# Chessbot_v8.net
KiCad netlist of a schematic drawn in EAGLE
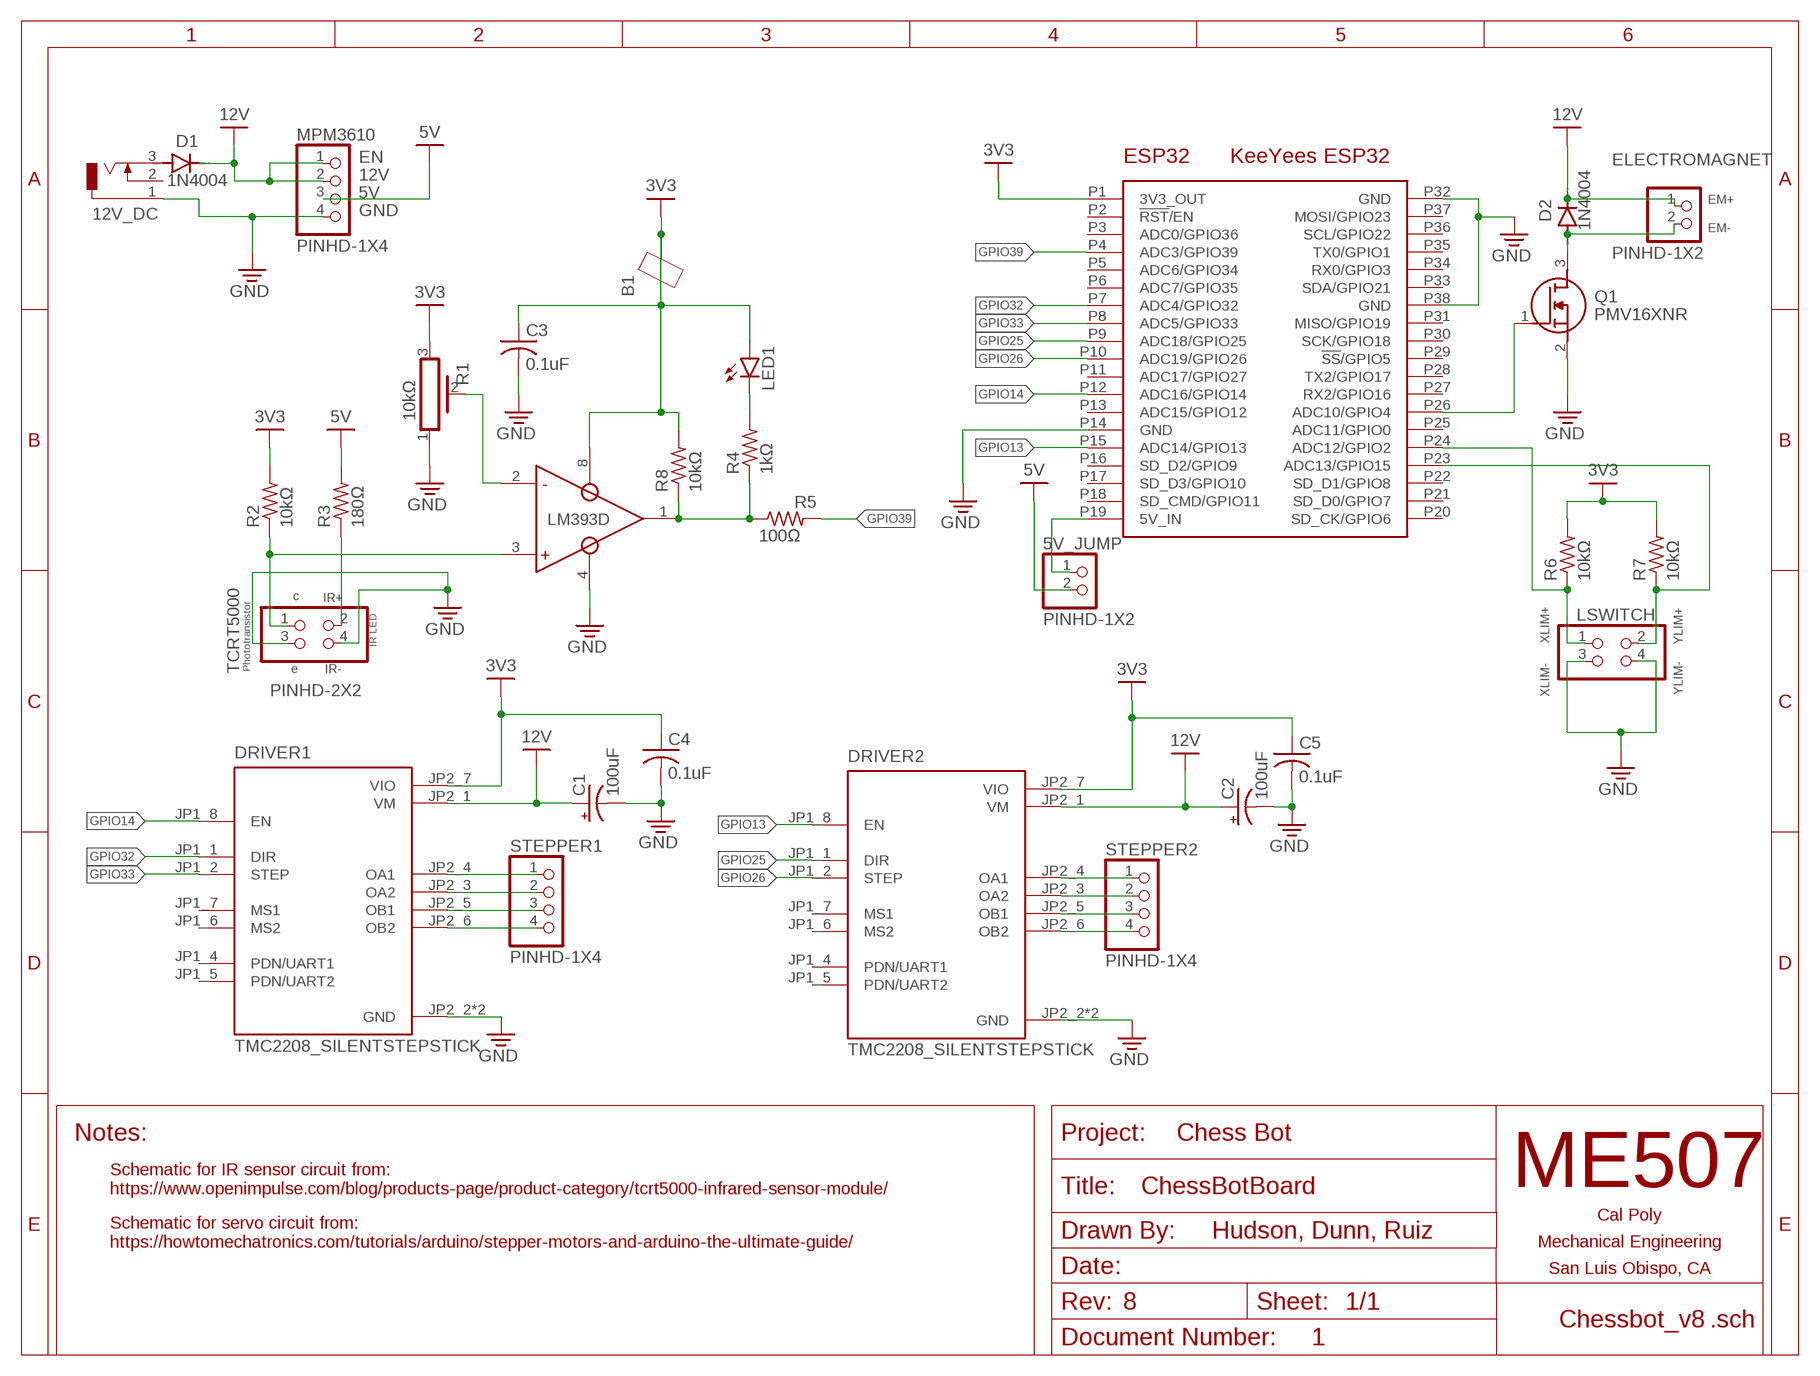
[diagram p0: schematic, sheet 1]

(export (version "E")
  (design (tool "Eeschema 10.0.6"))
  (components
    (comp (ref "5V_JUMP")
      (value "PINHD-1X2")
      (footprint "eagle-import:1X02")
      (libsource (lib "eagle-import") (part "PINHD-1X2"))
    )
    (comp (ref "12V_DC")
      (value "DCJ0303")
      (footprint "eagle-import:DCJ0303")
      (libsource (lib "eagle-import") (part "DCJ0303"))
    )
    (comp (ref "B1")
      (value "BEAD0805")
      (footprint "eagle-import:0805")
      (libsource (lib "eagle-import") (part "BEAD0805"))
    )
    (comp (ref "C1")
      (value "100uF")
      (footprint "eagle-import:E2,5-6")
      (libsource (lib "eagle-import") (part "CPOL-USE2.5-6"))
    )
    (comp (ref "C2")
      (value "100uF")
      (footprint "eagle-import:E2,5-6")
      (libsource (lib "eagle-import") (part "CPOL-USE2.5-6"))
    )
    (comp (ref "C3")
      (value "0.1uF")
      (footprint "eagle-import:C0805")
      (libsource (lib "eagle-import") (part "C-USC0805"))
    )
    (comp (ref "C4")
      (value "0.1uF")
      (footprint "eagle-import:C0805")
      (libsource (lib "eagle-import") (part "C-USC0805"))
    )
    (comp (ref "C5")
      (value "0.1uF")
      (footprint "eagle-import:C0805")
      (libsource (lib "eagle-import") (part "C-USC0805"))
    )
    (comp (ref "D1")
      (value "1N4004")
      (footprint "eagle-import:DO41-10")
      (libsource (lib "eagle-import") (part "1N4004"))
    )
    (comp (ref "D2")
      (value "1N4004")
      (footprint "eagle-import:DO41-10")
      (libsource (lib "eagle-import") (part "1N4004"))
    )
    (comp (ref "DRIVER1")
      (value "TMC2208_SILENTSTEPSTICK")
      (footprint "eagle-import:MODULE_TMC2208_SILENTSTEPSTICK")
      (fields (field (name "MF") "Trinamic Motion") (field (name "MP") "TMC2208 SILENTSTEPSTICK"))
      (libsource (lib "eagle-import") (part "TMC2208_SILENTSTEPSTICK"))
    )
    (comp (ref "DRIVER2")
      (value "TMC2208_SILENTSTEPSTICK")
      (footprint "eagle-import:MODULE_TMC2208_SILENTSTEPSTICK")
      (fields (field (name "MF") "Trinamic Motion") (field (name "MP") "TMC2208 SILENTSTEPSTICK"))
      (libsource (lib "eagle-import") (part "TMC2208_SILENTSTEPSTICK"))
    )
    (comp (ref "ELECTROMAGNET")
      (value "PINHD-1X2")
      (footprint "eagle-import:1X02")
      (libsource (lib "eagle-import") (part "PINHD-1X2"))
    )
    (comp (ref "ESP32")
      (value "KEEYEES_ESP32")
      (footprint "eagle-import:KEEYEES_ESP32")
      (libsource (lib "eagle-import") (part "KEEYEES_ESP32"))
    )
    (comp (ref "LED1")
      (value "LEDSMT1206")
      (footprint "eagle-import:1206")
      (libsource (lib "eagle-import") (part "LEDSMT1206"))
    )
    (comp (ref "LSWITCH")
      (value "PINHD-2X2")
      (footprint "eagle-import:2X02")
      (libsource (lib "eagle-import") (part "pinhead_325_PINHD-2X2"))
    )
    (comp (ref "MPM3610")
      (value "PINHD-1X4")
      (footprint "eagle-import:1X04")
      (libsource (lib "eagle-import") (part "PINHD-1X4"))
    )
    (comp (ref "Q1")
      (value "PMV16XNR")
      (footprint "eagle-import:SOT95P230X110-3N")
      (fields (field (name "MOUSER_PART_NUMBER") "771-PMV16XNR"))
      (libsource (lib "eagle-import") (part "PMV16XNR"))
    )
    (comp (ref "R1")
      (value "10kΩ")
      (footprint "eagle-import:PV36Z")
      (fields (field (name "MANUFACTURER") "BOURNS") (field (name "MPN") "PV36Z"))
      (libsource (lib "eagle-import") (part "PV36Z"))
    )
    (comp (ref "R2")
      (value "10kΩ")
      (footprint "eagle-import:R0805")
      (libsource (lib "eagle-import") (part "R-US_R0805"))
    )
    (comp (ref "R3")
      (value "180Ω")
      (footprint "eagle-import:R0805")
      (libsource (lib "eagle-import") (part "R-US_R0805"))
    )
    (comp (ref "R4")
      (value "1kΩ")
      (footprint "eagle-import:R0805")
      (libsource (lib "eagle-import") (part "R-US_R0805"))
    )
    (comp (ref "R5")
      (value "100Ω")
      (footprint "eagle-import:R0805")
      (libsource (lib "eagle-import") (part "R-US_R0805"))
    )
    (comp (ref "R6")
      (value "10kΩ")
      (footprint "eagle-import:R0805")
      (libsource (lib "eagle-import") (part "R-US_R0805"))
    )
    (comp (ref "R7")
      (value "10kΩ")
      (footprint "eagle-import:R0805")
      (libsource (lib "eagle-import") (part "R-US_R0805"))
    )
    (comp (ref "R8")
      (value "10kΩ")
      (footprint "eagle-import:R0805")
      (libsource (lib "eagle-import") (part "R-US_R0805"))
    )
    (comp (ref "STEPPER1")
      (value "PINHD-1X4")
      (footprint "eagle-import:1X04")
      (libsource (lib "eagle-import") (part "PINHD-1X4"))
    )
    (comp (ref "STEPPER2")
      (value "PINHD-1X4")
      (footprint "eagle-import:1X04")
      (libsource (lib "eagle-import") (part "PINHD-1X4"))
    )
    (comp (ref "TCRT5000")
      (value "PINHD-2X2")
      (footprint "eagle-import:2X02")
      (libsource (lib "eagle-import") (part "PINHD-2X2"))
    )
    (comp (ref "U$2")
      (value "LM393D")
      (footprint "eagle-import:LM393D")
      (libsource (lib "eagle-import") (part "LM393D"))
    )
  )
  (nets
    (net (code "1") (name "3V3") (class "Default")
      (node (ref "B1") (pin "1") (pinfunction "1_1") (pintype "bidirectional"))
      (node (ref "B1") (pin "2") (pinfunction "2_2") (pintype "bidirectional"))
      (node (ref "C3") (pin "1") (pinfunction "1_1") (pintype "passive"))
      (node (ref "C4") (pin "1") (pinfunction "1_1") (pintype "passive"))
      (node (ref "C5") (pin "1") (pinfunction "1_1") (pintype "passive"))
      (node (ref "DRIVER1") (pin "JP2_7") (pinfunction "VIO_JP2_7") (pintype "power_in"))
      (node (ref "DRIVER2") (pin "JP2_7") (pinfunction "VIO_JP2_7") (pintype "power_in"))
      (node (ref "ESP32") (pin "P1") (pinfunction "3V3_OUT_P1") (pintype "power_in"))
      (node (ref "LED1") (pin "A") (pinfunction "A_A") (pintype "passive"))
      (node (ref "R1") (pin "3") (pinfunction "P$3_3") (pintype "passive"))
      (node (ref "R2") (pin "2") (pinfunction "2_2") (pintype "passive"))
      (node (ref "R6") (pin "2") (pinfunction "2_2") (pintype "passive"))
      (node (ref "R7") (pin "2") (pinfunction "2_2") (pintype "passive"))
      (node (ref "R8") (pin "2") (pinfunction "2_2") (pintype "passive"))
      (node (ref "U$2") (pin "8") (pinfunction "VCC_8") (pintype "power_in"))
    )
    (net (code "2") (name "5V") (class "Default")
      (node (ref "5V_JUMP") (pin "2") (pinfunction "2_2") (pintype "passive"))
      (node (ref "MPM3610") (pin "3") (pinfunction "3_3") (pintype "passive"))
      (node (ref "R3") (pin "2") (pinfunction "2_2") (pintype "passive"))
    )
    (net (code "3") (name "12V") (class "Default")
      (node (ref "C1") (pin "+") (pinfunction "+_+") (pintype "passive"))
      (node (ref "C2") (pin "+") (pinfunction "+_+") (pintype "passive"))
      (node (ref "D1") (pin "C") (pinfunction "C_C") (pintype "passive"))
      (node (ref "D2") (pin "C") (pinfunction "C_C") (pintype "passive"))
      (node (ref "DRIVER1") (pin "JP2_1") (pinfunction "VM_JP2_1") (pintype "power_in"))
      (node (ref "DRIVER2") (pin "JP2_1") (pinfunction "VM_JP2_1") (pintype "power_in"))
      (node (ref "ELECTROMAGNET") (pin "1") (pinfunction "1_1") (pintype "passive"))
      (node (ref "MPM3610") (pin "1") (pinfunction "1_1") (pintype "passive"))
      (node (ref "MPM3610") (pin "2") (pinfunction "2_2") (pintype "passive"))
    )
    (net (code "4") (name "GND") (class "Default")
      (node (ref "12V_DC") (pin "1") (pinfunction "1_1") (pintype "passive"))
      (node (ref "C1") (pin "-") (pinfunction "-_-") (pintype "passive"))
      (node (ref "C2") (pin "-") (pinfunction "-_-") (pintype "passive"))
      (node (ref "C3") (pin "2") (pinfunction "2_2") (pintype "passive"))
      (node (ref "C4") (pin "2") (pinfunction "2_2") (pintype "passive"))
      (node (ref "C5") (pin "2") (pinfunction "2_2") (pintype "passive"))
      (node (ref "DRIVER1") (pin "JP2_2") (pinfunction "GND_JP2_2") (pintype "power_in"))
      (node (ref "DRIVER1") (pin "JP2_8") (pinfunction "GND_JP2_8") (pintype "power_in"))
      (node (ref "DRIVER2") (pin "JP2_2") (pinfunction "GND_JP2_2") (pintype "power_in"))
      (node (ref "DRIVER2") (pin "JP2_8") (pinfunction "GND_JP2_8") (pintype "power_in"))
      (node (ref "ESP32") (pin "P14") (pinfunction "GND_P14") (pintype "power_in"))
      (node (ref "ESP32") (pin "P32") (pinfunction "GND_P32") (pintype "power_in"))
      (node (ref "ESP32") (pin "P38") (pinfunction "GND_P38") (pintype "power_in"))
      (node (ref "LSWITCH") (pin "3") (pinfunction "3_3") (pintype "passive"))
      (node (ref "LSWITCH") (pin "4") (pinfunction "4_4") (pintype "passive"))
      (node (ref "MPM3610") (pin "4") (pinfunction "4_4") (pintype "passive"))
      (node (ref "Q1") (pin "2") (pinfunction "S_2") (pintype "bidirectional"))
      (node (ref "R1") (pin "1") (pinfunction "P$1_1") (pintype "passive"))
      (node (ref "TCRT5000") (pin "3") (pinfunction "3_3") (pintype "passive"))
      (node (ref "TCRT5000") (pin "4") (pinfunction "4_4") (pintype "passive"))
      (node (ref "U$2") (pin "4") (pinfunction "GND_4") (pintype "power_in"))
    )
    (net (code "5") (name "GPIO13") (class "Default")
      (node (ref "DRIVER2") (pin "JP1_8") (pinfunction "EN_JP1_8") (pintype "input"))
      (node (ref "ESP32") (pin "P15") (pinfunction "ADC14/GPIO13_P15") (pintype "bidirectional"))
    )
    (net (code "6") (name "GPIO14") (class "Default")
      (node (ref "DRIVER1") (pin "JP1_8") (pinfunction "EN_JP1_8") (pintype "input"))
      (node (ref "ESP32") (pin "P12") (pinfunction "ADC16/GPIO14_P12") (pintype "bidirectional"))
    )
    (net (code "7") (name "GPIO25") (class "Default")
      (node (ref "DRIVER2") (pin "JP1_1") (pinfunction "DIR_JP1_1") (pintype "input"))
      (node (ref "ESP32") (pin "P9") (pinfunction "ADC18/GPIO25_P9") (pintype "bidirectional"))
    )
    (net (code "8") (name "GPIO26") (class "Default")
      (node (ref "DRIVER2") (pin "JP1_2") (pinfunction "STEP_JP1_2") (pintype "input"))
      (node (ref "ESP32") (pin "P10") (pinfunction "ADC19/GPIO26_P10") (pintype "bidirectional"))
    )
    (net (code "9") (name "GPIO32") (class "Default")
      (node (ref "DRIVER1") (pin "JP1_1") (pinfunction "DIR_JP1_1") (pintype "input"))
      (node (ref "ESP32") (pin "P7") (pinfunction "ADC4/GPIO32_P7") (pintype "bidirectional"))
    )
    (net (code "10") (name "GPIO33") (class "Default")
      (node (ref "DRIVER1") (pin "JP1_2") (pinfunction "STEP_JP1_2") (pintype "input"))
      (node (ref "ESP32") (pin "P8") (pinfunction "ADC5/GPIO33_P8") (pintype "bidirectional"))
    )
    (net (code "11") (name "GPIO39") (class "Default")
      (node (ref "ESP32") (pin "P4") (pinfunction "ADC3/GPIO39_P4") (pintype "bidirectional"))
      (node (ref "R5") (pin "2") (pinfunction "2_2") (pintype "passive"))
    )
    (net (code "12") (name "Net-(12V_DC-Pad3)") (class "Default")
      (node (ref "12V_DC") (pin "3") (pinfunction "3_3") (pintype "passive"))
      (node (ref "D1") (pin "A") (pinfunction "A_A") (pintype "passive"))
    )
    (net (code "13") (name "Net-(DRIVER1-OA1)") (class "Default")
      (node (ref "DRIVER1") (pin "JP2_4") (pinfunction "OA1_JP2_4") (pintype "passive"))
      (node (ref "STEPPER1") (pin "1") (pinfunction "1_1") (pintype "passive"))
    )
    (net (code "14") (name "Net-(DRIVER1-OA2)") (class "Default")
      (node (ref "DRIVER1") (pin "JP2_3") (pinfunction "OA2_JP2_3") (pintype "passive"))
      (node (ref "STEPPER1") (pin "2") (pinfunction "2_2") (pintype "passive"))
    )
    (net (code "15") (name "Net-(DRIVER1-OB1)") (class "Default")
      (node (ref "DRIVER1") (pin "JP2_5") (pinfunction "OB1_JP2_5") (pintype "passive"))
      (node (ref "STEPPER1") (pin "3") (pinfunction "3_3") (pintype "passive"))
    )
    (net (code "16") (name "Net-(DRIVER1-OB2)") (class "Default")
      (node (ref "DRIVER1") (pin "JP2_6") (pinfunction "OB2_JP2_6") (pintype "passive"))
      (node (ref "STEPPER1") (pin "4") (pinfunction "4_4") (pintype "passive"))
    )
    (net (code "17") (name "Net-(DRIVER2-OA1)") (class "Default")
      (node (ref "DRIVER2") (pin "JP2_4") (pinfunction "OA1_JP2_4") (pintype "passive"))
      (node (ref "STEPPER2") (pin "1") (pinfunction "1_1") (pintype "passive"))
    )
    (net (code "18") (name "Net-(DRIVER2-OA2)") (class "Default")
      (node (ref "DRIVER2") (pin "JP2_3") (pinfunction "OA2_JP2_3") (pintype "passive"))
      (node (ref "STEPPER2") (pin "2") (pinfunction "2_2") (pintype "passive"))
    )
    (net (code "19") (name "Net-(DRIVER2-OB1)") (class "Default")
      (node (ref "DRIVER2") (pin "JP2_5") (pinfunction "OB1_JP2_5") (pintype "passive"))
      (node (ref "STEPPER2") (pin "3") (pinfunction "3_3") (pintype "passive"))
    )
    (net (code "20") (name "Net-(DRIVER2-OB2)") (class "Default")
      (node (ref "DRIVER2") (pin "JP2_6") (pinfunction "OB2_JP2_6") (pintype "passive"))
      (node (ref "STEPPER2") (pin "4") (pinfunction "4_4") (pintype "passive"))
    )
    (net (code "21") (name "Net-(ESP32-5V_IN)") (class "Default")
      (node (ref "5V_JUMP") (pin "1") (pinfunction "1_1") (pintype "passive"))
      (node (ref "ESP32") (pin "P19") (pinfunction "5V_IN_P19") (pintype "power_in"))
    )
    (net (code "22") (name "Net-(ESP32-ADC10{slash}GPIO4)") (class "Default")
      (node (ref "ESP32") (pin "P26") (pinfunction "ADC10/GPIO4_P26") (pintype "bidirectional"))
      (node (ref "Q1") (pin "1") (pinfunction "G_1") (pintype "bidirectional"))
    )
    (net (code "23") (name "Net-(ESP32-ADC12{slash}GPIO2)") (class "Default")
      (node (ref "ESP32") (pin "P24") (pinfunction "ADC12/GPIO2_P24") (pintype "bidirectional"))
      (node (ref "LSWITCH") (pin "1") (pinfunction "1_1") (pintype "passive"))
      (node (ref "R6") (pin "1") (pinfunction "1_1") (pintype "passive"))
    )
    (net (code "24") (name "Net-(ESP32-ADC13{slash}GPIO15)") (class "Default")
      (node (ref "ESP32") (pin "P23") (pinfunction "ADC13/GPIO15_P23") (pintype "bidirectional"))
      (node (ref "LSWITCH") (pin "2") (pinfunction "2_2") (pintype "passive"))
      (node (ref "R7") (pin "1") (pinfunction "1_1") (pintype "passive"))
    )
    (net (code "25") (name "Net-(LED1-PadC)") (class "Default")
      (node (ref "LED1") (pin "C") (pinfunction "C_C") (pintype "passive"))
      (node (ref "R4") (pin "2") (pinfunction "2_2") (pintype "passive"))
    )
    (net (code "26") (name "Net-(Q1-D)") (class "Default")
      (node (ref "D2") (pin "A") (pinfunction "A_A") (pintype "passive"))
      (node (ref "ELECTROMAGNET") (pin "2") (pinfunction "2_2") (pintype "passive"))
      (node (ref "Q1") (pin "3") (pinfunction "D_3") (pintype "bidirectional"))
    )
    (net (code "27") (name "Net-(R1-P$2)") (class "Default")
      (node (ref "R1") (pin "2") (pinfunction "P$2_2") (pintype "passive"))
      (node (ref "U$2") (pin "2") (pinfunction "IN-_2") (pintype "input"))
    )
    (net (code "28") (name "Net-(R3-Pad1)") (class "Default")
      (node (ref "R3") (pin "1") (pinfunction "1_1") (pintype "passive"))
      (node (ref "TCRT5000") (pin "2") (pinfunction "2_2") (pintype "passive"))
    )
    (net (code "29") (name "Net-(U$2B-IN+)") (class "Default")
      (node (ref "R2") (pin "1") (pinfunction "1_1") (pintype "passive"))
      (node (ref "TCRT5000") (pin "1") (pinfunction "1_1") (pintype "passive"))
      (node (ref "U$2") (pin "3") (pinfunction "IN+_3") (pintype "input"))
    )
    (net (code "30") (name "Net-(U$2B-OUT)") (class "Default")
      (node (ref "R4") (pin "1") (pinfunction "1_1") (pintype "passive"))
      (node (ref "R5") (pin "1") (pinfunction "1_1") (pintype "passive"))
      (node (ref "R8") (pin "1") (pinfunction "1_1") (pintype "passive"))
      (node (ref "U$2") (pin "1") (pinfunction "OUT_1") (pintype "output"))
    )
    (net (code "31") (name "unconnected-(12V_DC-Pad2)") (class "Default")
      (node (ref "12V_DC") (pin "2") (pinfunction "2_2") (pintype "passive"))
    )
    (net (code "32") (name "unconnected-(DRIVER1-MS1-PadJP1_7)") (class "Default")
      (node (ref "DRIVER1") (pin "JP1_7") (pinfunction "MS1_JP1_7") (pintype "input"))
    )
    (net (code "33") (name "unconnected-(DRIVER1-MS2-PadJP1_6)") (class "Default")
      (node (ref "DRIVER1") (pin "JP1_6") (pinfunction "MS2_JP1_6") (pintype "input"))
    )
    (net (code "34") (name "unconnected-(DRIVER1-PDN{slash}UART1-PadJP1_4)") (class "Default")
      (node (ref "DRIVER1") (pin "JP1_4") (pinfunction "PDN/UART1_JP1_4") (pintype "bidirectional"))
    )
    (net (code "35") (name "unconnected-(DRIVER1-PDN{slash}UART2-PadJP1_5)") (class "Default")
      (node (ref "DRIVER1") (pin "JP1_5") (pinfunction "PDN/UART2_JP1_5") (pintype "bidirectional"))
    )
    (net (code "36") (name "unconnected-(DRIVER2-MS1-PadJP1_7)") (class "Default")
      (node (ref "DRIVER2") (pin "JP1_7") (pinfunction "MS1_JP1_7") (pintype "input"))
    )
    (net (code "37") (name "unconnected-(DRIVER2-MS2-PadJP1_6)") (class "Default")
      (node (ref "DRIVER2") (pin "JP1_6") (pinfunction "MS2_JP1_6") (pintype "input"))
    )
    (net (code "38") (name "unconnected-(DRIVER2-PDN{slash}UART1-PadJP1_4)") (class "Default")
      (node (ref "DRIVER2") (pin "JP1_4") (pinfunction "PDN/UART1_JP1_4") (pintype "bidirectional"))
    )
    (net (code "39") (name "unconnected-(DRIVER2-PDN{slash}UART2-PadJP1_5)") (class "Default")
      (node (ref "DRIVER2") (pin "JP1_5") (pinfunction "PDN/UART2_JP1_5") (pintype "bidirectional"))
    )
    (net (code "40") (name "unconnected-(ESP32-ADC0{slash}GPIO36-PadP3)") (class "Default")
      (node (ref "ESP32") (pin "P3") (pinfunction "ADC0/GPIO36_P3") (pintype "bidirectional"))
    )
    (net (code "41") (name "unconnected-(ESP32-ADC6{slash}GPIO34-PadP5)") (class "Default")
      (node (ref "ESP32") (pin "P5") (pinfunction "ADC6/GPIO34_P5") (pintype "bidirectional"))
    )
    (net (code "42") (name "unconnected-(ESP32-ADC7{slash}GPIO35-PadP6)") (class "Default")
      (node (ref "ESP32") (pin "P6") (pinfunction "ADC7/GPIO35_P6") (pintype "bidirectional"))
    )
    (net (code "43") (name "unconnected-(ESP32-ADC11{slash}GPIO0-PadP25)") (class "Default")
      (node (ref "ESP32") (pin "P25") (pinfunction "ADC11/GPIO0_P25") (pintype "bidirectional"))
    )
    (net (code "44") (name "unconnected-(ESP32-ADC15{slash}GPIO12-PadP13)") (class "Default")
      (node (ref "ESP32") (pin "P13") (pinfunction "ADC15/GPIO12_P13") (pintype "bidirectional"))
    )
    (net (code "45") (name "unconnected-(ESP32-ADC17{slash}GPIO27-PadP11)") (class "Default")
      (node (ref "ESP32") (pin "P11") (pinfunction "ADC17/GPIO27_P11") (pintype "bidirectional"))
    )
    (net (code "46") (name "unconnected-(ESP32-MISO{slash}GPIO19-PadP31)") (class "Default")
      (node (ref "ESP32") (pin "P31") (pinfunction "MISO/GPIO19_P31") (pintype "bidirectional"))
    )
    (net (code "47") (name "unconnected-(ESP32-MOSI{slash}GPIO23-PadP37)") (class "Default")
      (node (ref "ESP32") (pin "P37") (pinfunction "MOSI/GPIO23_P37") (pintype "bidirectional"))
    )
    (net (code "48") (name "unconnected-(ESP32-RX0{slash}GPIO3-PadP34)") (class "Default")
      (node (ref "ESP32") (pin "P34") (pinfunction "RX0/GPIO3_P34") (pintype "bidirectional"))
    )
    (net (code "49") (name "unconnected-(ESP32-RX2{slash}GPIO16-PadP27)") (class "Default")
      (node (ref "ESP32") (pin "P27") (pinfunction "RX2/GPIO16_P27") (pintype "bidirectional"))
    )
    (net (code "50") (name "unconnected-(ESP32-SCK{slash}GPIO18-PadP30)") (class "Default")
      (node (ref "ESP32") (pin "P30") (pinfunction "SCK/GPIO18_P30") (pintype "bidirectional"))
    )
    (net (code "51") (name "unconnected-(ESP32-SCL{slash}GPIO22-PadP36)") (class "Default")
      (node (ref "ESP32") (pin "P36") (pinfunction "SCL/GPIO22_P36") (pintype "bidirectional"))
    )
    (net (code "52") (name "unconnected-(ESP32-SDA{slash}GPIO21-PadP33)") (class "Default")
      (node (ref "ESP32") (pin "P33") (pinfunction "SDA/GPIO21_P33") (pintype "bidirectional"))
    )
    (net (code "53") (name "unconnected-(ESP32-SD_CK{slash}GPIO6-PadP20)") (class "Default")
      (node (ref "ESP32") (pin "P20") (pinfunction "SD_CK/GPIO6_P20") (pintype "bidirectional"))
    )
    (net (code "54") (name "unconnected-(ESP32-SD_CMD{slash}GPIO11-PadP18)") (class "Default")
      (node (ref "ESP32") (pin "P18") (pinfunction "SD_CMD/GPIO11_P18") (pintype "bidirectional"))
    )
    (net (code "55") (name "unconnected-(ESP32-SD_D0{slash}GPIO7-PadP21)") (class "Default")
      (node (ref "ESP32") (pin "P21") (pinfunction "SD_D0/GPIO7_P21") (pintype "bidirectional"))
    )
    (net (code "56") (name "unconnected-(ESP32-SD_D1{slash}GPIO8-PadP22)") (class "Default")
      (node (ref "ESP32") (pin "P22") (pinfunction "SD_D1/GPIO8_P22") (pintype "bidirectional"))
    )
    (net (code "57") (name "unconnected-(ESP32-SD_D2{slash}GPIO9-PadP16)") (class "Default")
      (node (ref "ESP32") (pin "P16") (pinfunction "SD_D2/GPIO9_P16") (pintype "bidirectional"))
    )
    (net (code "58") (name "unconnected-(ESP32-SD_D3{slash}GPIO10-PadP17)") (class "Default")
      (node (ref "ESP32") (pin "P17") (pinfunction "SD_D3/GPIO10_P17") (pintype "bidirectional"))
    )
    (net (code "59") (name "unconnected-(ESP32-TX0{slash}GPIO1-PadP35)") (class "Default")
      (node (ref "ESP32") (pin "P35") (pinfunction "TX0/GPIO1_P35") (pintype "bidirectional"))
    )
    (net (code "60") (name "unconnected-(ESP32-TX2{slash}GPIO17-PadP28)") (class "Default")
      (node (ref "ESP32") (pin "P28") (pinfunction "TX2/GPIO17_P28") (pintype "bidirectional"))
    )
    (net (code "61") (name "unconnected-(ESP32-~{RST}{slash}EN-PadP2)") (class "Default")
      (node (ref "ESP32") (pin "P2") (pinfunction "~{RST}/EN_P2") (pintype "input"))
    )
    (net (code "62") (name "unconnected-(ESP32-~{SS}{slash}GPIO5-PadP29)") (class "Default")
      (node (ref "ESP32") (pin "P29") (pinfunction "~{SS}/GPIO5_P29") (pintype "bidirectional"))
    )
  )
)
